# conn_fan.net
KiCad netlist of a schematic drawn in Altium Designer
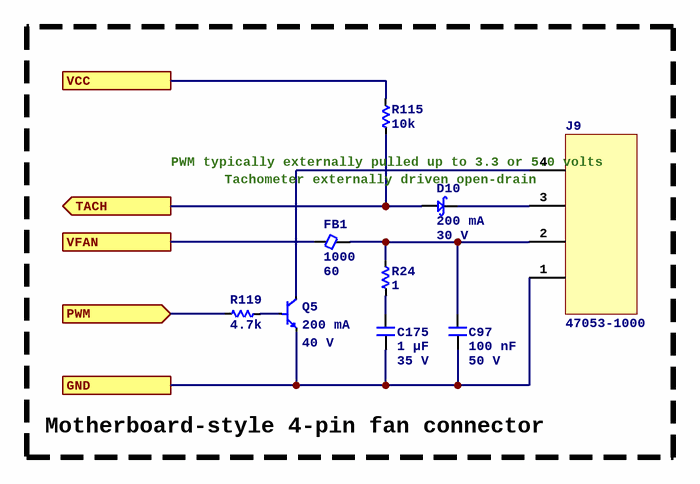
[diagram p0: conn_fan.SchDoc]

(export (version "E")
  (design (tool "Eeschema 10.0.6"))
  (components
    (comp (ref "C97")
      (value "CL05B104KB54PNC")
      (footprint "C0402")
      (fields
        (field (name "CAPACITANCE") "100 nF")
        (field (name "MANUFACTURER") "Samsung Electro-Mechanics")
        (field (name "VOLTAGE RATING") "50 V")
      )
      (libsource (lib "database") (part "__template_cap"))
    )
    (comp (ref "C175")
      (value "GMK107AB7105KAHT")
      (footprint "C0603")
      (fields
        (field (name "CAPACITANCE") "1 µF")
        (field (name "MANUFACTURER") "Taiyo Yuden")
        (field (name "VOLTAGE RATING") "35 V")
      )
      (libsource (lib "database") (part "__template_cap"))
    )
    (comp (ref "D10")
      (value "BAT54XV2T1G")
      (footprint "SOD523")
      (description "ON Semi BAT54XV2T1G; SMT Schottky Diode; 30V 200mA; 5ns; 2-Pin SOD-523")
      (fields
        (field (name "MANUFACTURER") "onsemi")
        (field (name "CURRENT") "200 mA")
        (field (name "VR") "30 V")
      )
      (libsource (lib "database") (part "__template_diode_schottky"))
    )
    (comp (ref "FB1")
      (value "MGGB2012M600HT-LF")
      (footprint "FB0805")
      (fields
        (field (name "MANUFACTURER") "microgate")
        (field (name "CURRENT RATING (MA)") "1000")
        (field (name "Z @ 100 MHZ") "60")
      )
      (libsource (lib "database") (part "__template_fb"))
    )
    (comp (ref "J9")
      (value "47053-1000")
      (footprint "MOLEX_KK254_4POS_VERT_0470531000")
      (fields (field (name "MANUFACTURER") "Molex"))
      (libsource (lib "database") (part "47053-1000"))
    )
    (comp (ref "Q5")
      (value "MMBT3904T")
      (footprint "3SOT523")
      (description "Bipolar (BJT) Transistor NPN 40 V 200 mA 300MHz 150 mW Surface Mount SOT-523")
      (fields
        (field (name "MANUFACTURER") "Shenzhen Slkormicro Semicon Co., Ltd.")
        (field (name "CURRENT") "200 mA")
        (field (name "VOLTAGE") "40 V")
      )
      (libsource (lib "database") (part "MMBT3904T"))
    )
    (comp (ref "R24")
      (value "1")
      (footprint "R0402")
      (fields
        (field (name "TOLERANCE") "1%")
        (field (name "MANUFACTURER PART NUMBER") "CRCW04021R00FKEDC")
        (field (name "MANUFACTURER") "Vishay Intertech")
      )
      (libsource (lib "database") (part "__template_resistor"))
    )
    (comp (ref "R115")
      (value "10k")
      (footprint "R0402")
      (fields
        (field (name "TOLERANCE") "1%")
        (field (name "MANUFACTURER PART NUMBER") "0402WGF1002TCE")
        (field (name "MANUFACTURER") "UNI-ROYAL(Uniroyal Elec)")
      )
      (libsource (lib "database") (part "__template_resistor"))
    )
    (comp (ref "R119")
      (value "4.7k")
      (footprint "R0402")
      (fields
        (field (name "TOLERANCE") "1%")
        (field (name "MANUFACTURER PART NUMBER") "0402WGF4701TCE")
        (field (name "MANUFACTURER") "UNI-ROYAL(Uniroyal Elec)")
      )
      (libsource (lib "database") (part "__template_resistor"))
    )
  )
  (nets
    (net (code "1") (name "/GND") (class "Default")
      (node (ref "C175") (pin "2") (pintype "passive"))
      (node (ref "C97") (pin "2") (pintype "passive"))
      (node (ref "J9") (pin "1") (pintype "passive"))
      (node (ref "Q5") (pin "2") (pinfunction "E_2") (pintype "passive"))
    )
    (net (code "2") (name "/PWM") (class "Default") (node (ref "R119") (pin "2") (pintype "passive")))
    (net (code "3") (name "/TACH") (class "Default")
      (node (ref "D10") (pin "1") (pintype "passive"))
      (node (ref "R115") (pin "2") (pintype "passive"))
    )
    (net (code "4") (name "/VCC") (class "Default") (node (ref "R115") (pin "1") (pintype "passive")))
    (net (code "5") (name "/VFAN") (class "Default") (node (ref "FB1") (pin "1") (pintype "passive")))
    (net (code "6") (name "Net-(C97-Pad1)") (class "Default")
      (node (ref "C97") (pin "1") (pintype "passive"))
      (node (ref "FB1") (pin "2") (pintype "passive"))
      (node (ref "J9") (pin "2") (pintype "passive"))
      (node (ref "R24") (pin "2") (pintype "passive"))
    )
    (net (code "7") (name "Net-(C175-Pad1)") (class "Default")
      (node (ref "C175") (pin "1") (pintype "passive"))
      (node (ref "R24") (pin "1") (pintype "passive"))
    )
    (net (code "8") (name "Net-(D10-Pad2)") (class "Default")
      (node (ref "D10") (pin "2") (pintype "passive"))
      (node (ref "J9") (pin "3") (pintype "passive"))
    )
    (net (code "9") (name "Net-(Q5-B)") (class "Default")
      (node (ref "Q5") (pin "1") (pinfunction "B_1") (pintype "passive"))
      (node (ref "R119") (pin "1") (pintype "passive"))
    )
    (net (code "10") (name "Net-(Q5-C)") (class "Default")
      (node (ref "J9") (pin "4") (pintype "passive"))
      (node (ref "Q5") (pin "3") (pinfunction "C_3") (pintype "passive"))
    )
  )
)
